# gnublin_ext_8080.net
KiCad netlist of a schematic drawn in EAGLE
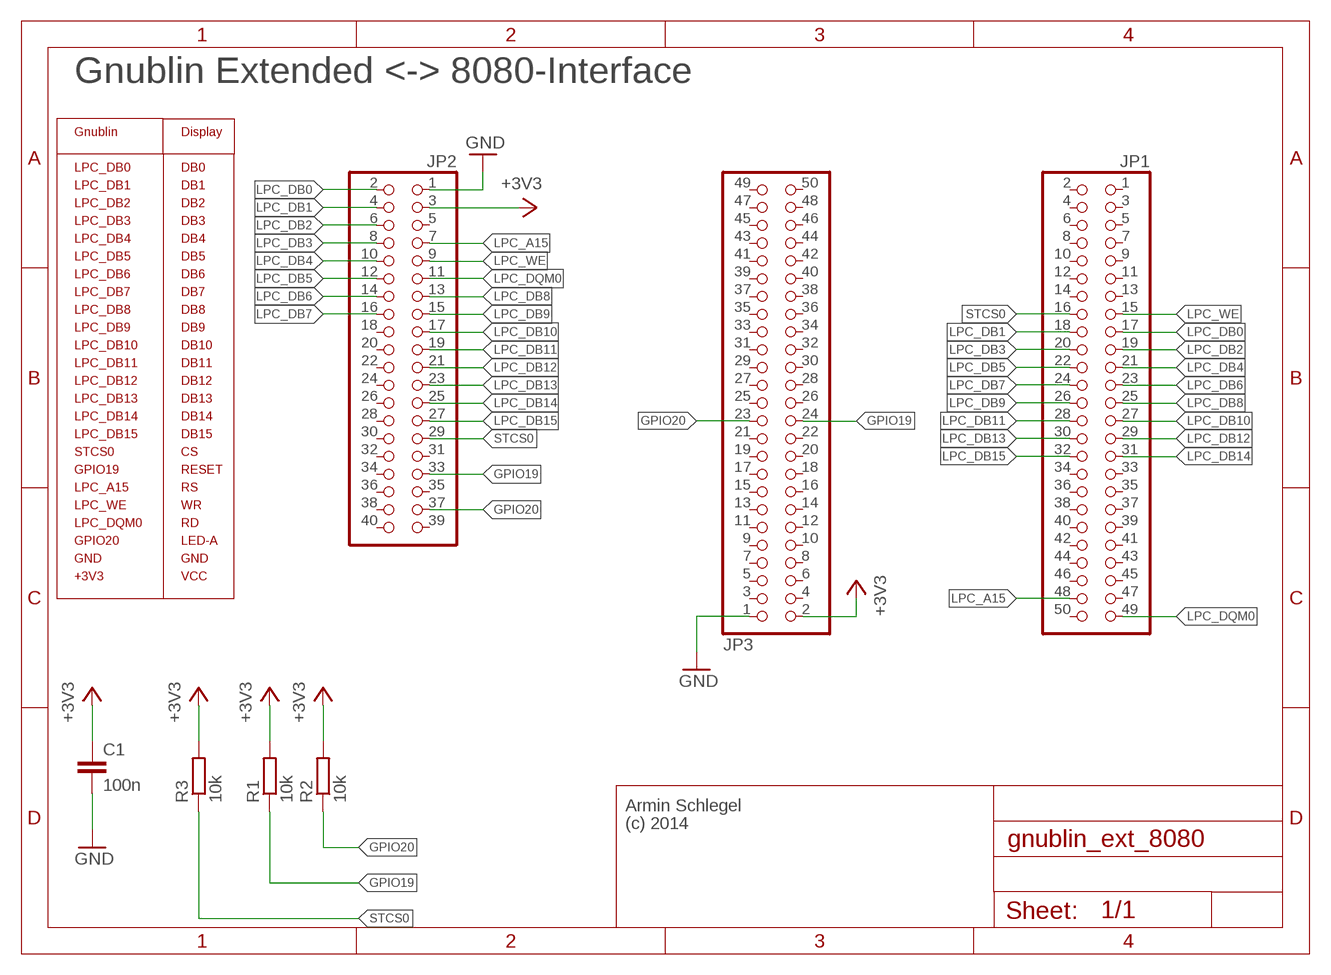
[diagram p0: schematic, sheet 1]

(export (version "E")
  (design (tool "Eeschema 10.0.6"))
  (components
    (comp (ref "C1")
      (value "100n")
      (footprint "eagle-import:C0805")
      (libsource (lib "eagle-import") (part "C-EUC0805"))
    )
    (comp (ref "JP1")
      (value "PINHD-2X25_2.54-SMD")
      (footprint "eagle-import:2X25SMD")
      (libsource (lib "eagle-import") (part "PINHD-2X25_2.54-SMD"))
    )
    (comp (ref "JP2")
      (value "PINHD-2X20")
      (footprint "eagle-import:2X20")
      (libsource (lib "eagle-import") (part "PINHD-2X20"))
    )
    (comp (ref "JP3")
      (value "PINHD-2X25_2.54-SMD")
      (footprint "eagle-import:2X25SMD")
      (libsource (lib "eagle-import") (part "PINHD-2X25_2.54-SMD"))
    )
    (comp (ref "R1")
      (value "10k")
      (footprint "eagle-import:R0603")
      (libsource (lib "eagle-import") (part "R-EU_R0603"))
    )
    (comp (ref "R2")
      (value "10k")
      (footprint "eagle-import:R0603")
      (libsource (lib "eagle-import") (part "R-EU_R0603"))
    )
    (comp (ref "R3")
      (value "10k")
      (footprint "eagle-import:R0603")
      (libsource (lib "eagle-import") (part "R-EU_R0603"))
    )
  )
  (nets
    (net (code "1") (name "+3V3") (class "Default")
      (node (ref "C1") (pin "1") (pinfunction "1_1") (pintype "passive"))
      (node (ref "JP2") (pin "3") (pinfunction "3_3") (pintype "passive"))
      (node (ref "JP3") (pin "2") (pinfunction "2_2") (pintype "passive"))
      (node (ref "R1") (pin "2") (pinfunction "2_2") (pintype "passive"))
      (node (ref "R2") (pin "2") (pinfunction "2_2") (pintype "passive"))
      (node (ref "R3") (pin "2") (pinfunction "2_2") (pintype "passive"))
    )
    (net (code "2") (name "GND") (class "Default")
      (node (ref "C1") (pin "2") (pinfunction "2_2") (pintype "passive"))
      (node (ref "JP2") (pin "1") (pinfunction "1_1") (pintype "passive"))
      (node (ref "JP3") (pin "1") (pinfunction "1_1") (pintype "passive"))
    )
    (net (code "3") (name "GPIO19") (class "Default")
      (node (ref "JP2") (pin "33") (pinfunction "33_33") (pintype "passive"))
      (node (ref "JP3") (pin "24") (pinfunction "24_24") (pintype "passive"))
      (node (ref "R1") (pin "1") (pinfunction "1_1") (pintype "passive"))
    )
    (net (code "4") (name "GPIO20") (class "Default")
      (node (ref "JP2") (pin "37") (pinfunction "37_37") (pintype "passive"))
      (node (ref "JP3") (pin "23") (pinfunction "23_23") (pintype "passive"))
      (node (ref "R2") (pin "1") (pinfunction "1_1") (pintype "passive"))
    )
    (net (code "5") (name "LPC_A15") (class "Default")
      (node (ref "JP1") (pin "48") (pinfunction "48_48") (pintype "passive"))
      (node (ref "JP2") (pin "7") (pinfunction "7_7") (pintype "passive"))
    )
    (net (code "6") (name "LPC_DB0") (class "Default")
      (node (ref "JP1") (pin "17") (pinfunction "17_17") (pintype "passive"))
      (node (ref "JP2") (pin "2") (pinfunction "2_2") (pintype "passive"))
    )
    (net (code "7") (name "LPC_DB1") (class "Default")
      (node (ref "JP1") (pin "18") (pinfunction "18_18") (pintype "passive"))
      (node (ref "JP2") (pin "4") (pinfunction "4_4") (pintype "passive"))
    )
    (net (code "8") (name "LPC_DB2") (class "Default")
      (node (ref "JP1") (pin "19") (pinfunction "19_19") (pintype "passive"))
      (node (ref "JP2") (pin "6") (pinfunction "6_6") (pintype "passive"))
    )
    (net (code "9") (name "LPC_DB3") (class "Default")
      (node (ref "JP1") (pin "20") (pinfunction "20_20") (pintype "passive"))
      (node (ref "JP2") (pin "8") (pinfunction "8_8") (pintype "passive"))
    )
    (net (code "10") (name "LPC_DB4") (class "Default")
      (node (ref "JP1") (pin "21") (pinfunction "21_21") (pintype "passive"))
      (node (ref "JP2") (pin "10") (pinfunction "10_10") (pintype "passive"))
    )
    (net (code "11") (name "LPC_DB5") (class "Default")
      (node (ref "JP1") (pin "22") (pinfunction "22_22") (pintype "passive"))
      (node (ref "JP2") (pin "12") (pinfunction "12_12") (pintype "passive"))
    )
    (net (code "12") (name "LPC_DB6") (class "Default")
      (node (ref "JP1") (pin "23") (pinfunction "23_23") (pintype "passive"))
      (node (ref "JP2") (pin "14") (pinfunction "14_14") (pintype "passive"))
    )
    (net (code "13") (name "LPC_DB7") (class "Default")
      (node (ref "JP1") (pin "24") (pinfunction "24_24") (pintype "passive"))
      (node (ref "JP2") (pin "16") (pinfunction "16_16") (pintype "passive"))
    )
    (net (code "14") (name "LPC_DB8") (class "Default")
      (node (ref "JP1") (pin "25") (pinfunction "25_25") (pintype "passive"))
      (node (ref "JP2") (pin "13") (pinfunction "13_13") (pintype "passive"))
    )
    (net (code "15") (name "LPC_DB9") (class "Default")
      (node (ref "JP1") (pin "26") (pinfunction "26_26") (pintype "passive"))
      (node (ref "JP2") (pin "15") (pinfunction "15_15") (pintype "passive"))
    )
    (net (code "16") (name "LPC_DB10") (class "Default")
      (node (ref "JP1") (pin "27") (pinfunction "27_27") (pintype "passive"))
      (node (ref "JP2") (pin "17") (pinfunction "17_17") (pintype "passive"))
    )
    (net (code "17") (name "LPC_DB11") (class "Default")
      (node (ref "JP1") (pin "28") (pinfunction "28_28") (pintype "passive"))
      (node (ref "JP2") (pin "19") (pinfunction "19_19") (pintype "passive"))
    )
    (net (code "18") (name "LPC_DB12") (class "Default")
      (node (ref "JP1") (pin "29") (pinfunction "29_29") (pintype "passive"))
      (node (ref "JP2") (pin "21") (pinfunction "21_21") (pintype "passive"))
    )
    (net (code "19") (name "LPC_DB13") (class "Default")
      (node (ref "JP1") (pin "30") (pinfunction "30_30") (pintype "passive"))
      (node (ref "JP2") (pin "23") (pinfunction "23_23") (pintype "passive"))
    )
    (net (code "20") (name "LPC_DB14") (class "Default")
      (node (ref "JP1") (pin "31") (pinfunction "31_31") (pintype "passive"))
      (node (ref "JP2") (pin "25") (pinfunction "25_25") (pintype "passive"))
    )
    (net (code "21") (name "LPC_DB15") (class "Default")
      (node (ref "JP1") (pin "32") (pinfunction "32_32") (pintype "passive"))
      (node (ref "JP2") (pin "27") (pinfunction "27_27") (pintype "passive"))
    )
    (net (code "22") (name "LPC_DQM0") (class "Default")
      (node (ref "JP1") (pin "49") (pinfunction "49_49") (pintype "passive"))
      (node (ref "JP2") (pin "11") (pinfunction "11_11") (pintype "passive"))
    )
    (net (code "23") (name "LPC_WE") (class "Default")
      (node (ref "JP1") (pin "15") (pinfunction "15_15") (pintype "passive"))
      (node (ref "JP2") (pin "9") (pinfunction "9_9") (pintype "passive"))
    )
    (net (code "24") (name "STCS0") (class "Default")
      (node (ref "JP1") (pin "16") (pinfunction "16_16") (pintype "passive"))
      (node (ref "JP2") (pin "29") (pinfunction "29_29") (pintype "passive"))
      (node (ref "R3") (pin "1") (pinfunction "1_1") (pintype "passive"))
    )
    (net (code "25") (name "unconnected-(JP1-Pad1)") (class "Default")
      (node (ref "JP1") (pin "1") (pinfunction "1_1") (pintype "passive"))
    )
    (net (code "26") (name "unconnected-(JP1-Pad2)") (class "Default")
      (node (ref "JP1") (pin "2") (pinfunction "2_2") (pintype "passive"))
    )
    (net (code "27") (name "unconnected-(JP1-Pad3)") (class "Default")
      (node (ref "JP1") (pin "3") (pinfunction "3_3") (pintype "passive"))
    )
    (net (code "28") (name "unconnected-(JP1-Pad4)") (class "Default")
      (node (ref "JP1") (pin "4") (pinfunction "4_4") (pintype "passive"))
    )
    (net (code "29") (name "unconnected-(JP1-Pad5)") (class "Default")
      (node (ref "JP1") (pin "5") (pinfunction "5_5") (pintype "passive"))
    )
    (net (code "30") (name "unconnected-(JP1-Pad6)") (class "Default")
      (node (ref "JP1") (pin "6") (pinfunction "6_6") (pintype "passive"))
    )
    (net (code "31") (name "unconnected-(JP1-Pad7)") (class "Default")
      (node (ref "JP1") (pin "7") (pinfunction "7_7") (pintype "passive"))
    )
    (net (code "32") (name "unconnected-(JP1-Pad8)") (class "Default")
      (node (ref "JP1") (pin "8") (pinfunction "8_8") (pintype "passive"))
    )
    (net (code "33") (name "unconnected-(JP1-Pad9)") (class "Default")
      (node (ref "JP1") (pin "9") (pinfunction "9_9") (pintype "passive"))
    )
    (net (code "34") (name "unconnected-(JP1-Pad10)") (class "Default")
      (node (ref "JP1") (pin "10") (pinfunction "10_10") (pintype "passive"))
    )
    (net (code "35") (name "unconnected-(JP1-Pad11)") (class "Default")
      (node (ref "JP1") (pin "11") (pinfunction "11_11") (pintype "passive"))
    )
    (net (code "36") (name "unconnected-(JP1-Pad12)") (class "Default")
      (node (ref "JP1") (pin "12") (pinfunction "12_12") (pintype "passive"))
    )
    (net (code "37") (name "unconnected-(JP1-Pad13)") (class "Default")
      (node (ref "JP1") (pin "13") (pinfunction "13_13") (pintype "passive"))
    )
    (net (code "38") (name "unconnected-(JP1-Pad14)") (class "Default")
      (node (ref "JP1") (pin "14") (pinfunction "14_14") (pintype "passive"))
    )
    (net (code "39") (name "unconnected-(JP1-Pad33)") (class "Default")
      (node (ref "JP1") (pin "33") (pinfunction "33_33") (pintype "passive"))
    )
    (net (code "40") (name "unconnected-(JP1-Pad34)") (class "Default")
      (node (ref "JP1") (pin "34") (pinfunction "34_34") (pintype "passive"))
    )
    (net (code "41") (name "unconnected-(JP1-Pad35)") (class "Default")
      (node (ref "JP1") (pin "35") (pinfunction "35_35") (pintype "passive"))
    )
    (net (code "42") (name "unconnected-(JP1-Pad36)") (class "Default")
      (node (ref "JP1") (pin "36") (pinfunction "36_36") (pintype "passive"))
    )
    (net (code "43") (name "unconnected-(JP1-Pad37)") (class "Default")
      (node (ref "JP1") (pin "37") (pinfunction "37_37") (pintype "passive"))
    )
    (net (code "44") (name "unconnected-(JP1-Pad38)") (class "Default")
      (node (ref "JP1") (pin "38") (pinfunction "38_38") (pintype "passive"))
    )
    (net (code "45") (name "unconnected-(JP1-Pad39)") (class "Default")
      (node (ref "JP1") (pin "39") (pinfunction "39_39") (pintype "passive"))
    )
    (net (code "46") (name "unconnected-(JP1-Pad40)") (class "Default")
      (node (ref "JP1") (pin "40") (pinfunction "40_40") (pintype "passive"))
    )
    (net (code "47") (name "unconnected-(JP1-Pad41)") (class "Default")
      (node (ref "JP1") (pin "41") (pinfunction "41_41") (pintype "passive"))
    )
    (net (code "48") (name "unconnected-(JP1-Pad42)") (class "Default")
      (node (ref "JP1") (pin "42") (pinfunction "42_42") (pintype "passive"))
    )
    (net (code "49") (name "unconnected-(JP1-Pad43)") (class "Default")
      (node (ref "JP1") (pin "43") (pinfunction "43_43") (pintype "passive"))
    )
    (net (code "50") (name "unconnected-(JP1-Pad44)") (class "Default")
      (node (ref "JP1") (pin "44") (pinfunction "44_44") (pintype "passive"))
    )
    (net (code "51") (name "unconnected-(JP1-Pad45)") (class "Default")
      (node (ref "JP1") (pin "45") (pinfunction "45_45") (pintype "passive"))
    )
    (net (code "52") (name "unconnected-(JP1-Pad46)") (class "Default")
      (node (ref "JP1") (pin "46") (pinfunction "46_46") (pintype "passive"))
    )
    (net (code "53") (name "unconnected-(JP1-Pad47)") (class "Default")
      (node (ref "JP1") (pin "47") (pinfunction "47_47") (pintype "passive"))
    )
    (net (code "54") (name "unconnected-(JP1-Pad50)") (class "Default")
      (node (ref "JP1") (pin "50") (pinfunction "50_50") (pintype "passive"))
    )
    (net (code "55") (name "unconnected-(JP2-Pad5)") (class "Default")
      (node (ref "JP2") (pin "5") (pinfunction "5_5") (pintype "passive"))
    )
    (net (code "56") (name "unconnected-(JP2-Pad18)") (class "Default")
      (node (ref "JP2") (pin "18") (pinfunction "18_18") (pintype "passive"))
    )
    (net (code "57") (name "unconnected-(JP2-Pad20)") (class "Default")
      (node (ref "JP2") (pin "20") (pinfunction "20_20") (pintype "passive"))
    )
    (net (code "58") (name "unconnected-(JP2-Pad22)") (class "Default")
      (node (ref "JP2") (pin "22") (pinfunction "22_22") (pintype "passive"))
    )
    (net (code "59") (name "unconnected-(JP2-Pad24)") (class "Default")
      (node (ref "JP2") (pin "24") (pinfunction "24_24") (pintype "passive"))
    )
    (net (code "60") (name "unconnected-(JP2-Pad26)") (class "Default")
      (node (ref "JP2") (pin "26") (pinfunction "26_26") (pintype "passive"))
    )
    (net (code "61") (name "unconnected-(JP2-Pad28)") (class "Default")
      (node (ref "JP2") (pin "28") (pinfunction "28_28") (pintype "passive"))
    )
    (net (code "62") (name "unconnected-(JP2-Pad30)") (class "Default")
      (node (ref "JP2") (pin "30") (pinfunction "30_30") (pintype "passive"))
    )
    (net (code "63") (name "unconnected-(JP2-Pad31)") (class "Default")
      (node (ref "JP2") (pin "31") (pinfunction "31_31") (pintype "passive"))
    )
    (net (code "64") (name "unconnected-(JP2-Pad32)") (class "Default")
      (node (ref "JP2") (pin "32") (pinfunction "32_32") (pintype "passive"))
    )
    (net (code "65") (name "unconnected-(JP2-Pad34)") (class "Default")
      (node (ref "JP2") (pin "34") (pinfunction "34_34") (pintype "passive"))
    )
    (net (code "66") (name "unconnected-(JP2-Pad35)") (class "Default")
      (node (ref "JP2") (pin "35") (pinfunction "35_35") (pintype "passive"))
    )
    (net (code "67") (name "unconnected-(JP2-Pad36)") (class "Default")
      (node (ref "JP2") (pin "36") (pinfunction "36_36") (pintype "passive"))
    )
    (net (code "68") (name "unconnected-(JP2-Pad38)") (class "Default")
      (node (ref "JP2") (pin "38") (pinfunction "38_38") (pintype "passive"))
    )
    (net (code "69") (name "unconnected-(JP2-Pad39)") (class "Default")
      (node (ref "JP2") (pin "39") (pinfunction "39_39") (pintype "passive"))
    )
    (net (code "70") (name "unconnected-(JP2-Pad40)") (class "Default")
      (node (ref "JP2") (pin "40") (pinfunction "40_40") (pintype "passive"))
    )
    (net (code "71") (name "unconnected-(JP3-Pad3)") (class "Default")
      (node (ref "JP3") (pin "3") (pinfunction "3_3") (pintype "passive"))
    )
    (net (code "72") (name "unconnected-(JP3-Pad4)") (class "Default")
      (node (ref "JP3") (pin "4") (pinfunction "4_4") (pintype "passive"))
    )
    (net (code "73") (name "unconnected-(JP3-Pad5)") (class "Default")
      (node (ref "JP3") (pin "5") (pinfunction "5_5") (pintype "passive"))
    )
    (net (code "74") (name "unconnected-(JP3-Pad6)") (class "Default")
      (node (ref "JP3") (pin "6") (pinfunction "6_6") (pintype "passive"))
    )
    (net (code "75") (name "unconnected-(JP3-Pad7)") (class "Default")
      (node (ref "JP3") (pin "7") (pinfunction "7_7") (pintype "passive"))
    )
    (net (code "76") (name "unconnected-(JP3-Pad8)") (class "Default")
      (node (ref "JP3") (pin "8") (pinfunction "8_8") (pintype "passive"))
    )
    (net (code "77") (name "unconnected-(JP3-Pad9)") (class "Default")
      (node (ref "JP3") (pin "9") (pinfunction "9_9") (pintype "passive"))
    )
    (net (code "78") (name "unconnected-(JP3-Pad10)") (class "Default")
      (node (ref "JP3") (pin "10") (pinfunction "10_10") (pintype "passive"))
    )
    (net (code "79") (name "unconnected-(JP3-Pad11)") (class "Default")
      (node (ref "JP3") (pin "11") (pinfunction "11_11") (pintype "passive"))
    )
    (net (code "80") (name "unconnected-(JP3-Pad12)") (class "Default")
      (node (ref "JP3") (pin "12") (pinfunction "12_12") (pintype "passive"))
    )
    (net (code "81") (name "unconnected-(JP3-Pad13)") (class "Default")
      (node (ref "JP3") (pin "13") (pinfunction "13_13") (pintype "passive"))
    )
    (net (code "82") (name "unconnected-(JP3-Pad14)") (class "Default")
      (node (ref "JP3") (pin "14") (pinfunction "14_14") (pintype "passive"))
    )
    (net (code "83") (name "unconnected-(JP3-Pad15)") (class "Default")
      (node (ref "JP3") (pin "15") (pinfunction "15_15") (pintype "passive"))
    )
    (net (code "84") (name "unconnected-(JP3-Pad16)") (class "Default")
      (node (ref "JP3") (pin "16") (pinfunction "16_16") (pintype "passive"))
    )
    (net (code "85") (name "unconnected-(JP3-Pad17)") (class "Default")
      (node (ref "JP3") (pin "17") (pinfunction "17_17") (pintype "passive"))
    )
    (net (code "86") (name "unconnected-(JP3-Pad18)") (class "Default")
      (node (ref "JP3") (pin "18") (pinfunction "18_18") (pintype "passive"))
    )
    (net (code "87") (name "unconnected-(JP3-Pad19)") (class "Default")
      (node (ref "JP3") (pin "19") (pinfunction "19_19") (pintype "passive"))
    )
    (net (code "88") (name "unconnected-(JP3-Pad20)") (class "Default")
      (node (ref "JP3") (pin "20") (pinfunction "20_20") (pintype "passive"))
    )
    (net (code "89") (name "unconnected-(JP3-Pad21)") (class "Default")
      (node (ref "JP3") (pin "21") (pinfunction "21_21") (pintype "passive"))
    )
    (net (code "90") (name "unconnected-(JP3-Pad22)") (class "Default")
      (node (ref "JP3") (pin "22") (pinfunction "22_22") (pintype "passive"))
    )
    (net (code "91") (name "unconnected-(JP3-Pad25)") (class "Default")
      (node (ref "JP3") (pin "25") (pinfunction "25_25") (pintype "passive"))
    )
    (net (code "92") (name "unconnected-(JP3-Pad26)") (class "Default")
      (node (ref "JP3") (pin "26") (pinfunction "26_26") (pintype "passive"))
    )
    (net (code "93") (name "unconnected-(JP3-Pad27)") (class "Default")
      (node (ref "JP3") (pin "27") (pinfunction "27_27") (pintype "passive"))
    )
    (net (code "94") (name "unconnected-(JP3-Pad28)") (class "Default")
      (node (ref "JP3") (pin "28") (pinfunction "28_28") (pintype "passive"))
    )
    (net (code "95") (name "unconnected-(JP3-Pad29)") (class "Default")
      (node (ref "JP3") (pin "29") (pinfunction "29_29") (pintype "passive"))
    )
    (net (code "96") (name "unconnected-(JP3-Pad30)") (class "Default")
      (node (ref "JP3") (pin "30") (pinfunction "30_30") (pintype "passive"))
    )
    (net (code "97") (name "unconnected-(JP3-Pad31)") (class "Default")
      (node (ref "JP3") (pin "31") (pinfunction "31_31") (pintype "passive"))
    )
    (net (code "98") (name "unconnected-(JP3-Pad32)") (class "Default")
      (node (ref "JP3") (pin "32") (pinfunction "32_32") (pintype "passive"))
    )
    (net (code "99") (name "unconnected-(JP3-Pad33)") (class "Default")
      (node (ref "JP3") (pin "33") (pinfunction "33_33") (pintype "passive"))
    )
    (net (code "100") (name "unconnected-(JP3-Pad34)") (class "Default")
      (node (ref "JP3") (pin "34") (pinfunction "34_34") (pintype "passive"))
    )
    (net (code "101") (name "unconnected-(JP3-Pad35)") (class "Default")
      (node (ref "JP3") (pin "35") (pinfunction "35_35") (pintype "passive"))
    )
    (net (code "102") (name "unconnected-(JP3-Pad36)") (class "Default")
      (node (ref "JP3") (pin "36") (pinfunction "36_36") (pintype "passive"))
    )
    (net (code "103") (name "unconnected-(JP3-Pad37)") (class "Default")
      (node (ref "JP3") (pin "37") (pinfunction "37_37") (pintype "passive"))
    )
    (net (code "104") (name "unconnected-(JP3-Pad38)") (class "Default")
      (node (ref "JP3") (pin "38") (pinfunction "38_38") (pintype "passive"))
    )
    (net (code "105") (name "unconnected-(JP3-Pad39)") (class "Default")
      (node (ref "JP3") (pin "39") (pinfunction "39_39") (pintype "passive"))
    )
    (net (code "106") (name "unconnected-(JP3-Pad40)") (class "Default")
      (node (ref "JP3") (pin "40") (pinfunction "40_40") (pintype "passive"))
    )
    (net (code "107") (name "unconnected-(JP3-Pad41)") (class "Default")
      (node (ref "JP3") (pin "41") (pinfunction "41_41") (pintype "passive"))
    )
    (net (code "108") (name "unconnected-(JP3-Pad42)") (class "Default")
      (node (ref "JP3") (pin "42") (pinfunction "42_42") (pintype "passive"))
    )
    (net (code "109") (name "unconnected-(JP3-Pad43)") (class "Default")
      (node (ref "JP3") (pin "43") (pinfunction "43_43") (pintype "passive"))
    )
    (net (code "110") (name "unconnected-(JP3-Pad44)") (class "Default")
      (node (ref "JP3") (pin "44") (pinfunction "44_44") (pintype "passive"))
    )
    (net (code "111") (name "unconnected-(JP3-Pad45)") (class "Default")
      (node (ref "JP3") (pin "45") (pinfunction "45_45") (pintype "passive"))
    )
    (net (code "112") (name "unconnected-(JP3-Pad46)") (class "Default")
      (node (ref "JP3") (pin "46") (pinfunction "46_46") (pintype "passive"))
    )
    (net (code "113") (name "unconnected-(JP3-Pad47)") (class "Default")
      (node (ref "JP3") (pin "47") (pinfunction "47_47") (pintype "passive"))
    )
    (net (code "114") (name "unconnected-(JP3-Pad48)") (class "Default")
      (node (ref "JP3") (pin "48") (pinfunction "48_48") (pintype "passive"))
    )
    (net (code "115") (name "unconnected-(JP3-Pad49)") (class "Default")
      (node (ref "JP3") (pin "49") (pinfunction "49_49") (pintype "passive"))
    )
    (net (code "116") (name "unconnected-(JP3-Pad50)") (class "Default")
      (node (ref "JP3") (pin "50") (pinfunction "50_50") (pintype "passive"))
    )
  )
)
